# PowerSupply.net
KiCad netlist of a schematic drawn in Altium Designer
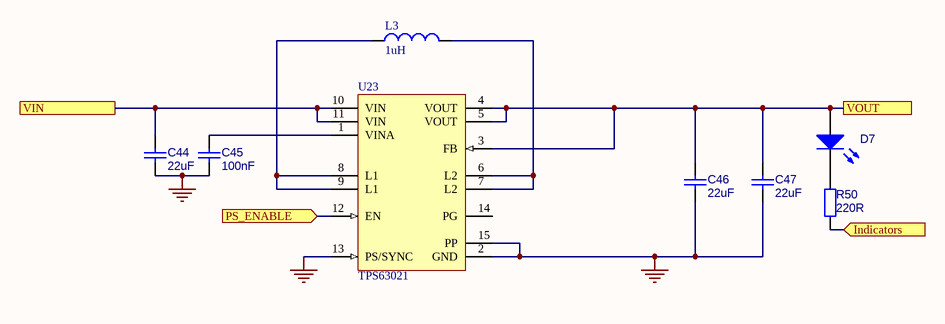
[diagram p0: PowerSupply.SchDoc]

(export (version "E")
  (design (tool "Eeschema 10.0.6"))
  (components
    (comp (ref "C44")
      (value "22uF")
      (footprint "0603_CAP UF HD")
      (description "Capacitor")
      (fields (field (name "MANUFACTURER") "MuRata"))
      (libsource (lib "Workshop Library 2010_06_24") (part "Cap"))
    )
    (comp (ref "C45")
      (value "100nF")
      (footprint "0603_CAP UF HD")
      (description "Capacitor")
      (libsource (lib "Workshop Library 2010_06_24") (part "Cap"))
    )
    (comp (ref "C46")
      (value "22uF")
      (footprint "0603_CAP UF HD")
      (description "Capacitor")
      (fields (field (name "MANUFACTURER") "MuRata"))
      (libsource (lib "Workshop Library 2010_06_24") (part "Cap"))
    )
    (comp (ref "C47")
      (value "22uF")
      (footprint "0603_CAP UF HD")
      (description "Capacitor")
      (fields (field (name "MANUFACTURER") "MuRata"))
      (libsource (lib "Workshop Library 2010_06_24") (part "Cap"))
    )
    (comp (ref "D7")
      (value "~")
      (footprint "LED 3mm Red")
      (description "LED")
      (libsource (lib "Workshop Library 2010_06_24") (part "LED"))
    )
    (comp (ref "L3")
      (value "1uH")
      (footprint "252012")
      (description "Inductor")
      (fields (field (name "MANUFACTURER") "Samsung Electro-Mechanics"))
      (libsource (lib "Workshop Library 2010_06_24") (part "Inductor"))
    )
    (comp (ref "R50")
      (value "220R")
      (footprint "0603-RESISTOR HD")
      (description "Resistor")
      (libsource (lib "Workshop Library 2010_06_24") (part "Resistor"))
    )
    (comp (ref "U23")
      (value "TPS63021")
      (footprint "DSJ14-4000X1580TP_V")
      (fields (field (name "MANUFACTURER") "Texas Instruments"))
      (libsource (lib "MegaPhone") (part "TPS63020DSJ14"))
    )
  )
  (nets
    (net (code "1") (name "/Indicators") (class "Default")
      (node (ref "R50") (pin "2") (pinfunction "2_2") (pintype "passive"))
    )
    (net (code "2") (name "/PS_ENABLE") (class "Default")
      (node (ref "U23") (pin "12") (pinfunction "EN_12") (pintype "input"))
    )
    (net (code "3") (name "/VIN") (class "Default")
      (node (ref "C44") (pin "1") (pinfunction "1_1") (pintype "passive"))
      (node (ref "U23") (pin "10") (pinfunction "VIN_10") (pintype "power_in"))
      (node (ref "U23") (pin "11") (pinfunction "VIN_11") (pintype "power_in"))
    )
    (net (code "4") (name "/VOUT") (class "Default")
      (node (ref "C46") (pin "1") (pinfunction "1_1") (pintype "passive"))
      (node (ref "C47") (pin "1") (pinfunction "1_1") (pintype "passive"))
      (node (ref "D7") (pin "A") (pinfunction "A_A") (pintype "passive"))
      (node (ref "U23") (pin "3") (pinfunction "FB_3") (pintype "input"))
      (node (ref "U23") (pin "4") (pinfunction "VOUT_4") (pintype "power_in"))
      (node (ref "U23") (pin "5") (pinfunction "VOUT_5") (pintype "power_in"))
    )
    (net (code "5") (name "GND") (class "Default")
      (node (ref "C44") (pin "2") (pinfunction "2_2") (pintype "passive"))
      (node (ref "C45") (pin "2") (pinfunction "2_2") (pintype "passive"))
      (node (ref "C46") (pin "2") (pinfunction "2_2") (pintype "passive"))
      (node (ref "C47") (pin "2") (pinfunction "2_2") (pintype "passive"))
      (node (ref "U23") (pin "13") (pinfunction "PS/SYNC_13") (pintype "input"))
      (node (ref "U23") (pin "15") (pinfunction "PP_15") (pintype "power_in"))
      (node (ref "U23") (pin "2") (pinfunction "GND_2") (pintype "power_in"))
    )
    (net (code "6") (name "Net-(D7-PadK)") (class "Default")
      (node (ref "D7") (pin "K") (pinfunction "K_K") (pintype "passive"))
      (node (ref "R50") (pin "1") (pinfunction "1_1") (pintype "passive"))
    )
    (net (code "7") (name "Net-(L3-Pad1)") (class "Default")
      (node (ref "L3") (pin "1") (pinfunction "1_1") (pintype "passive"))
      (node (ref "U23") (pin "8") (pinfunction "L1_8") (pintype "passive"))
      (node (ref "U23") (pin "9") (pinfunction "L1_9") (pintype "passive"))
    )
    (net (code "8") (name "Net-(L3-Pad2)") (class "Default")
      (node (ref "L3") (pin "2") (pinfunction "2_2") (pintype "passive"))
      (node (ref "U23") (pin "6") (pinfunction "L2_6") (pintype "passive"))
      (node (ref "U23") (pin "7") (pinfunction "L2_7") (pintype "passive"))
    )
    (net (code "9") (name "Net-(U23-VINA)") (class "Default")
      (node (ref "C45") (pin "1") (pinfunction "1_1") (pintype "passive"))
      (node (ref "U23") (pin "1") (pinfunction "VINA_1") (pintype "power_in"))
    )
    (net (code "10") (name "unconnected-(U23-PG-Pad14)") (class "Default")
      (node (ref "U23") (pin "14") (pinfunction "PG_14") (pintype "open_collector"))
    )
  )
)
